# ProProject_Buck-Boost_1_2024-04-12.net
KiCad netlist of a schematic drawn in EasyEDA Pro
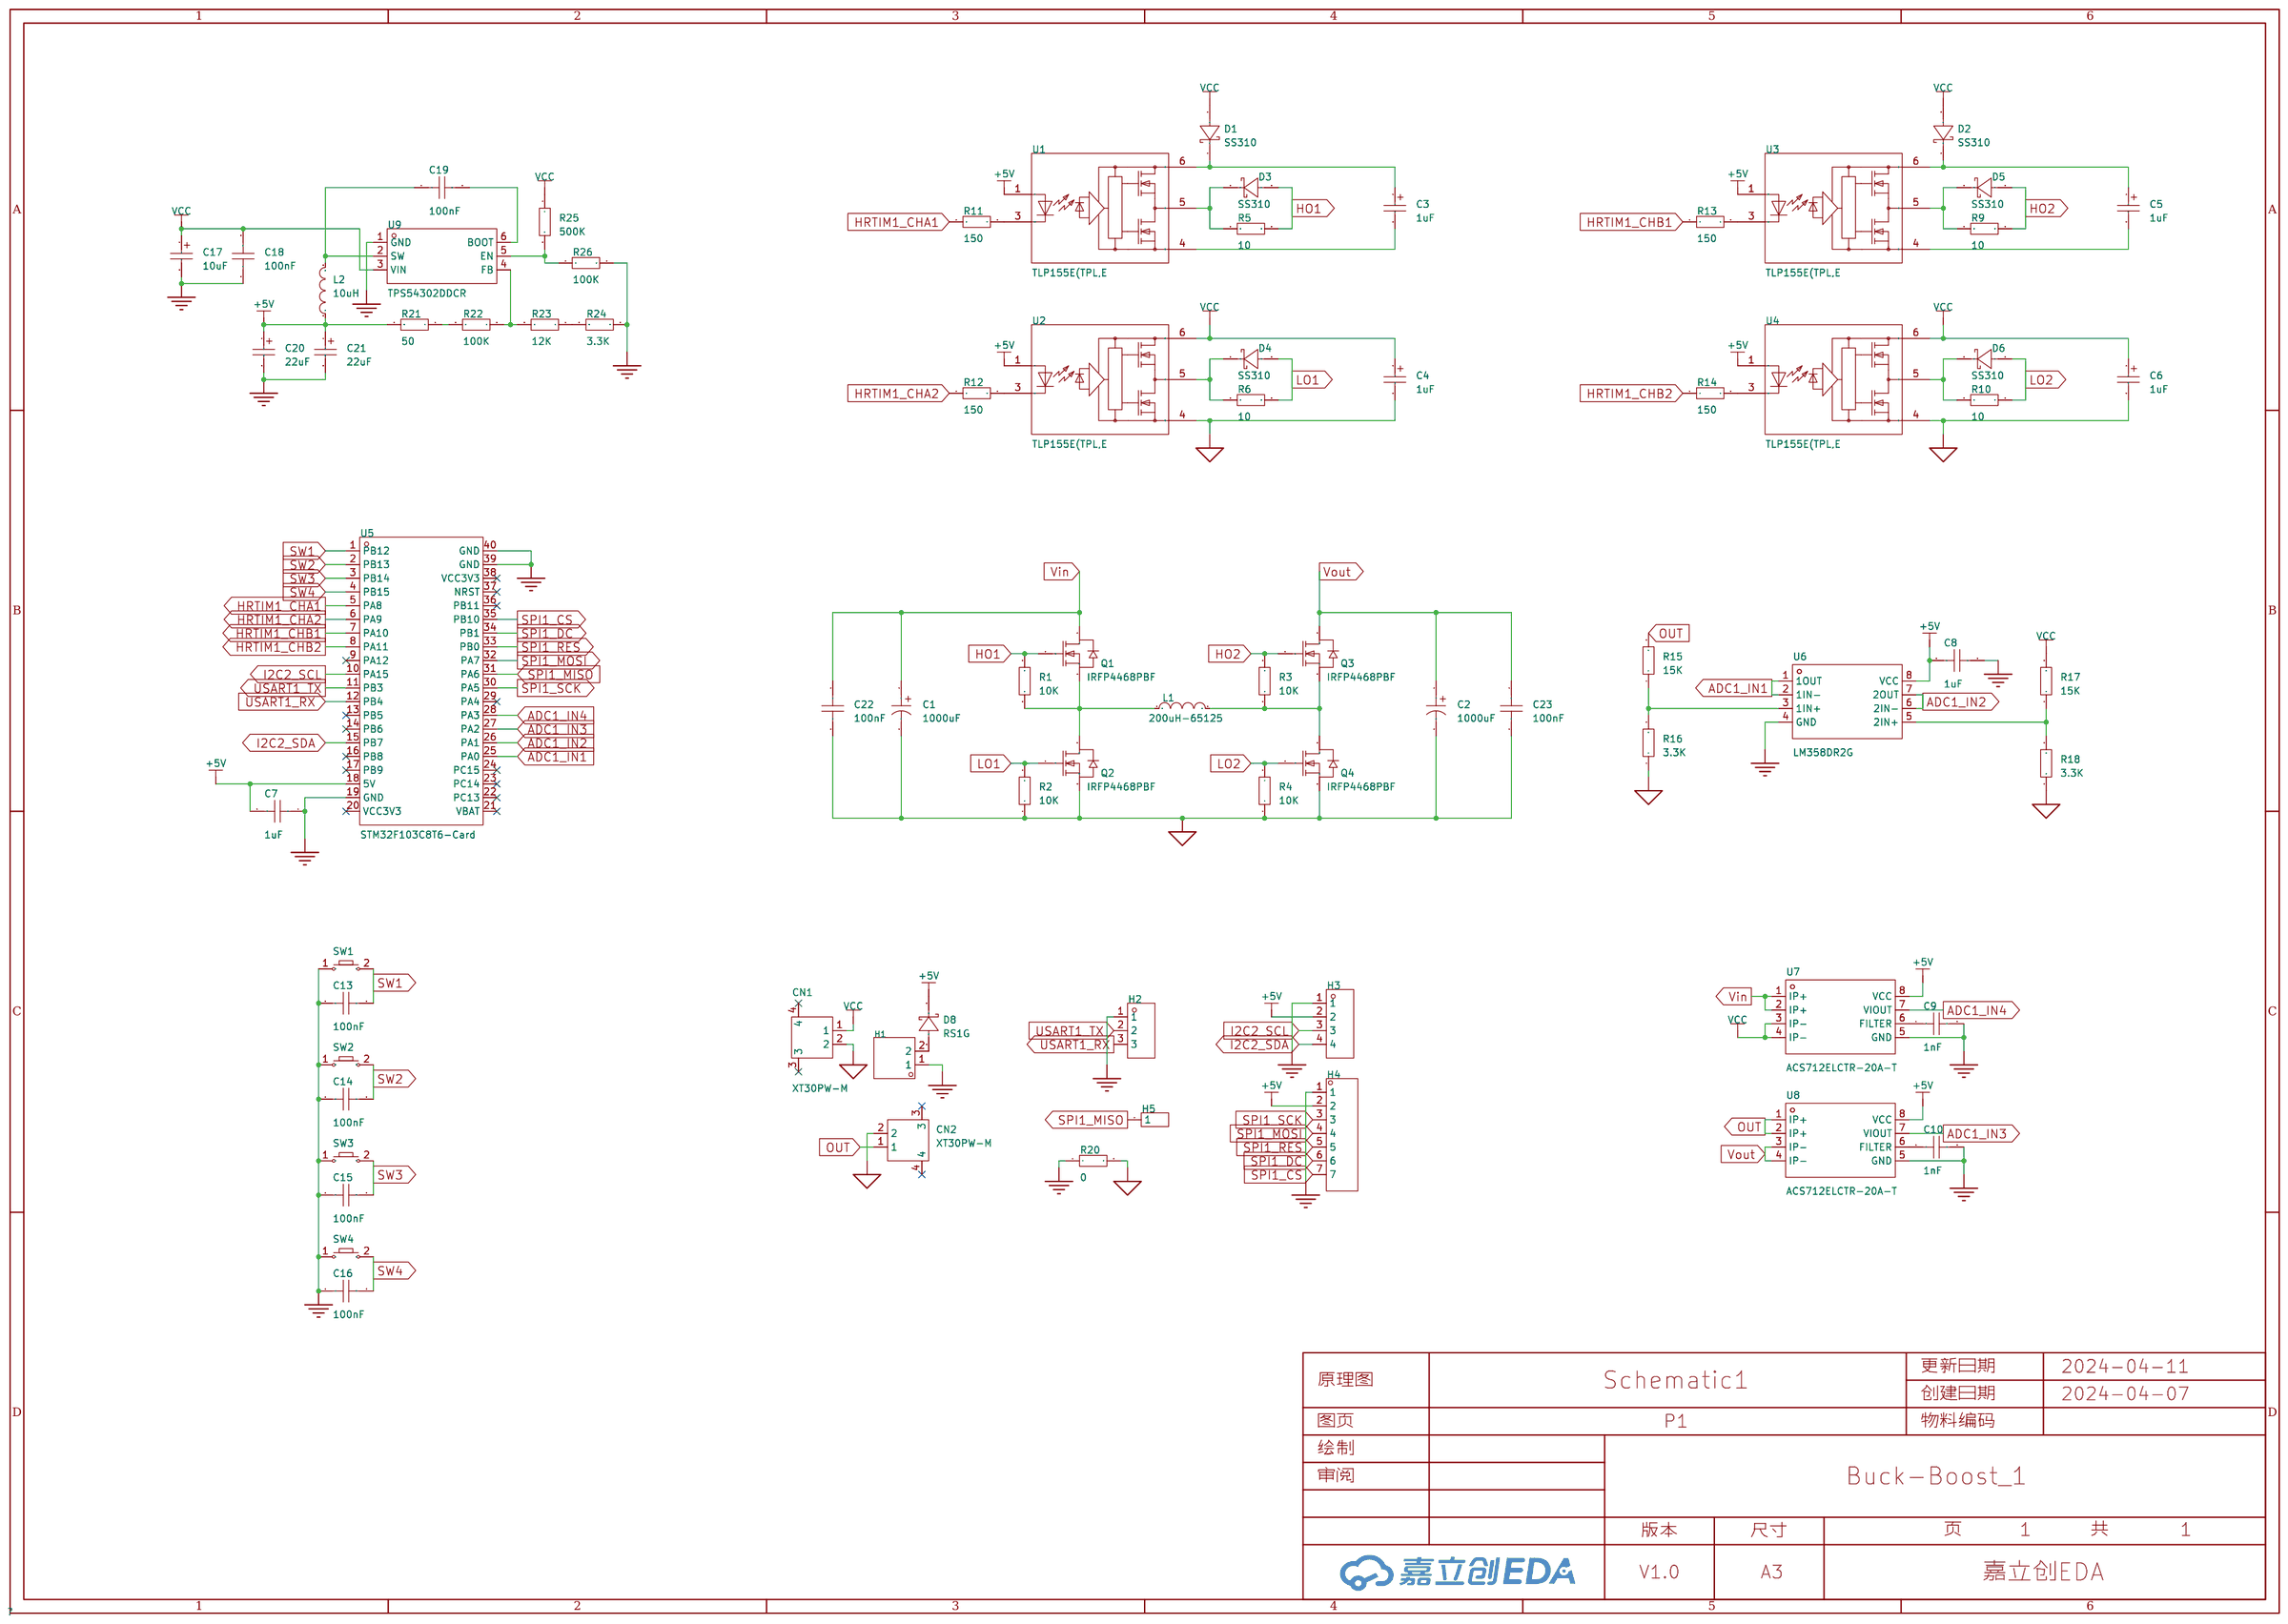
[diagram p0: schematic sheet]

(export (version "E")
  (design (tool "Eeschema 10.0.6"))
  (components
    (comp (ref "C1")
      (value "1000uF")
      (footprint "easyedapro:CAP-TH_BD16.0-P7.50-D1.5-FD")
      (description "容值:470uF;精度:±20%;额定电压:120V;纹波电流:-;等效串联电阻:-;")
      (fields (field (name "Manufacturer Part") "KF102M050I250A") (field (name "Manufacturer") "CapXon(丰宾)"))
      (libsource (lib "easyedapro") (part "ERS2BM471L35OT"))
    )
    (comp (ref "C2")
      (value "1000uF")
      (footprint "easyedapro:CAP-TH_BD16.0-P7.50-D1.5-FD")
      (description "容值:470uF;精度:±20%;额定电压:120V;纹波电流:-;等效串联电阻:-;")
      (fields (field (name "Manufacturer Part") "KF102M050I250A") (field (name "Manufacturer") "CapXon(丰宾)"))
      (libsource (lib "easyedapro") (part "ERS2BM471L35OT"))
    )
    (comp (ref "C3")
      (value "1uF")
      (footprint "easyedapro:CASE-A_3216")
      (description "容值:1uF;精度:±10%;额定电压:35V;等效串联电阻:7.5Ω@100kHz;")
      (fields (field (name "Manufacturer Part") "TAJA105K035RNJ") (field (name "Manufacturer") "Kyocera AVX"))
      (libsource (lib "easyedapro") (part "TAJA105K035RNJ"))
    )
    (comp (ref "C4")
      (value "1uF")
      (footprint "easyedapro:CASE-A_3216")
      (description "容值:1uF;精度:±10%;额定电压:35V;等效串联电阻:7.5Ω@100kHz;")
      (fields (field (name "Manufacturer Part") "TAJA105K035RNJ") (field (name "Manufacturer") "Kyocera AVX"))
      (libsource (lib "easyedapro") (part "TAJA105K035RNJ"))
    )
    (comp (ref "C5")
      (value "1uF")
      (footprint "easyedapro:CASE-A_3216")
      (description "容值:1uF;精度:±10%;额定电压:35V;等效串联电阻:7.5Ω@100kHz;")
      (fields (field (name "Manufacturer Part") "TAJA105K035RNJ") (field (name "Manufacturer") "Kyocera AVX"))
      (libsource (lib "easyedapro") (part "TAJA105K035RNJ"))
    )
    (comp (ref "C6")
      (value "1uF")
      (footprint "easyedapro:CASE-A_3216")
      (description "容值:1uF;精度:±10%;额定电压:35V;等效串联电阻:7.5Ω@100kHz;")
      (fields (field (name "Manufacturer Part") "TAJA105K035RNJ") (field (name "Manufacturer") "Kyocera AVX"))
      (libsource (lib "easyedapro") (part "TAJA105K035RNJ"))
    )
    (comp (ref "C7")
      (value "1uF")
      (footprint "easyedapro:C0805")
      (libsource (lib "easyedapro") (part "CapAcitance"))
    )
    (comp (ref "C8")
      (value "1uF")
      (footprint "easyedapro:C0805")
      (libsource (lib "easyedapro") (part "CapAcitance"))
    )
    (comp (ref "C9")
      (value "1nF")
      (footprint "easyedapro:C0805")
      (libsource (lib "easyedapro") (part "CapAcitance"))
    )
    (comp (ref "C10")
      (value "1nF")
      (footprint "easyedapro:C0805")
      (libsource (lib "easyedapro") (part "CapAcitance"))
    )
    (comp (ref "C13")
      (value "100nF")
      (footprint "easyedapro:C0805")
      (libsource (lib "easyedapro") (part "CapAcitance"))
    )
    (comp (ref "C14")
      (value "100nF")
      (footprint "easyedapro:C0805")
      (libsource (lib "easyedapro") (part "CapAcitance"))
    )
    (comp (ref "C15")
      (value "100nF")
      (footprint "easyedapro:C0805")
      (libsource (lib "easyedapro") (part "CapAcitance"))
    )
    (comp (ref "C16")
      (value "100nF")
      (footprint "easyedapro:C0805")
      (libsource (lib "easyedapro") (part "CapAcitance"))
    )
    (comp (ref "C17")
      (value "10uF")
      (footprint "easyedapro:CAP-SMD_L3.5-W2.8-R-RD")
      (description "容值:10uF;精度:±10%;额定电压:25V;等效串联电阻:2.5Ω@100kHz;")
      (fields (field (name "Manufacturer Part") "TAJB106K025RNJ") (field (name "Manufacturer") "Kyocera AVX"))
      (libsource (lib "easyedapro") (part "TAJB106K025RNJ"))
    )
    (comp (ref "C18")
      (value "100nF")
      (footprint "easyedapro:C0805")
      (libsource (lib "easyedapro") (part "CapAcitance"))
    )
    (comp (ref "C19")
      (value "100nF")
      (footprint "easyedapro:C0805")
      (libsource (lib "easyedapro") (part "CapAcitance"))
    )
    (comp (ref "C20")
      (value "22uF")
      (footprint "easyedapro:CASE-B_3528")
      (description "容值:22uF;精度:±10%;额定电压:16V;等效串联电阻:2.3Ω@100kHz;")
      (fields (field (name "Manufacturer Part") "TAJB226K016RNJ") (field (name "Manufacturer") "Kyocera AVX"))
      (libsource (lib "easyedapro") (part "TAJB226K016RNJ"))
    )
    (comp (ref "C21")
      (value "22uF")
      (footprint "easyedapro:CASE-B_3528")
      (description "容值:22uF;精度:±10%;额定电压:16V;等效串联电阻:2.3Ω@100kHz;")
      (fields (field (name "Manufacturer Part") "TAJB226K016RNJ") (field (name "Manufacturer") "Kyocera AVX"))
      (libsource (lib "easyedapro") (part "TAJB226K016RNJ"))
    )
    (comp (ref "C22")
      (value "100nF")
      (footprint "easyedapro:C0805")
      (libsource (lib "easyedapro") (part "CapAcitance"))
    )
    (comp (ref "C23")
      (value "100nF")
      (footprint "easyedapro:C0805")
      (libsource (lib "easyedapro") (part "CapAcitance"))
    )
    (comp (ref "CN1")
      (value "XT30PW-M")
      (footprint "easyedapro:CONN-TH_XT30PW-M")
      (description "类别:-;类型1:-;")
      (fields (field (name "Manufacturer") "AMASS(艾迈斯)"))
      (libsource (lib "easyedapro") (part "XT30PW-M"))
    )
    (comp (ref "CN2")
      (value "XT30PW-M")
      (footprint "easyedapro:CONN-TH_XT30PW-M")
      (description "类别:-;类型1:-;")
      (fields (field (name "Manufacturer") "AMASS(艾迈斯)"))
      (libsource (lib "easyedapro") (part "XT30PW-M"))
    )
    (comp (ref "D1")
      (value "SS310")
      (footprint "easyedapro:SMC_L6.9-W5.9-LS7.9-RD")
      (fields (field (name "Manufacturer") "MDD"))
      (libsource (lib "easyedapro") (part "SS56_C5161914"))
    )
    (comp (ref "D2")
      (value "SS310")
      (footprint "easyedapro:SMC_L6.9-W5.9-LS7.9-RD")
      (fields (field (name "Manufacturer") "MDD"))
      (libsource (lib "easyedapro") (part "SS56_C5161914"))
    )
    (comp (ref "D3")
      (value "SS310")
      (footprint "easyedapro:SMC_L6.9-W5.9-LS7.9-RD")
      (fields (field (name "Manufacturer") "MDD"))
      (libsource (lib "easyedapro") (part "SS56_C5161914"))
    )
    (comp (ref "D4")
      (value "SS310")
      (footprint "easyedapro:SMC_L6.9-W5.9-LS7.9-RD")
      (fields (field (name "Manufacturer") "MDD"))
      (libsource (lib "easyedapro") (part "SS56_C5161914"))
    )
    (comp (ref "D5")
      (value "SS310")
      (footprint "easyedapro:SMC_L6.9-W5.9-LS7.9-RD")
      (fields (field (name "Manufacturer") "MDD"))
      (libsource (lib "easyedapro") (part "SS56_C5161914"))
    )
    (comp (ref "D6")
      (value "SS310")
      (footprint "easyedapro:SMC_L6.9-W5.9-LS7.9-RD")
      (fields (field (name "Manufacturer") "MDD"))
      (libsource (lib "easyedapro") (part "SS56_C5161914"))
    )
    (comp (ref "D8")
      (value "RS1G")
      (footprint "easyedapro:SMC_L6.9-W5.9-LS7.9-RD")
      (fields (field (name "Manufacturer") "宏迦橙"))
      (libsource (lib "easyedapro") (part "SS56_C5161914"))
    )
    (comp (ref "H1")
      (value "~")
      (footprint "easyedapro:HDR-TH_2P-P2.54-V-M-1")
      (libsource (lib "easyedapro") (part "210S-1*2P L=11.6MMGold-plated black"))
    )
    (comp (ref "H2")
      (value "~")
      (footprint "easyedapro:HDR-TH_3P-P2.54-V-M")
      (libsource (lib "easyedapro") (part "PZ254V-11-03P_C2937625"))
    )
    (comp (ref "H3")
      (value "~")
      (footprint "easyedapro:HDR-TH_4P-P2.54-V-F")
      (libsource (lib "easyedapro") (part "2.54-1*4P母"))
    )
    (comp (ref "H4")
      (value "~")
      (footprint "easyedapro:HDR-TH_7P-P2.54-V-F")
      (libsource (lib "easyedapro") (part "220S-1*7P H=8.5MM Ytype Gold-plated"))
    )
    (comp (ref "H5")
      (value "~")
      (footprint "easyedapro:HDR-TH_1P-V-M_XKB_X4611WV-01I-C28D40")
      (libsource (lib "easyedapro") (part "HDR_1x1"))
    )
    (comp (ref "L1")
      (value "200uH-65125")
      (footprint "easyedapro:IND-TH_200UH-65125")
      (libsource (lib "easyedapro") (part "200UH-65125"))
    )
    (comp (ref "L2")
      (value "10uH")
      (footprint "easyedapro:IND-SMD_L7.3-W6.8")
      (description "电感值:10uH;精度:±20%;额定电流:4.5A;饱和电流(Isat):5.5A;类型:一体成型电感;")
      (fields (field (name "Manufacturer Part") "FXL0630-100-M") (field (name "Manufacturer") "cjiang(长江微电)"))
      (libsource (lib "easyedapro") (part "FXL0630-100-M"))
    )
    (comp (ref "Q1")
      (value "IRFP4468PBF")
      (footprint "easyedapro:TO-247AC-3_L15.8-W5.0-P5.46-L")
      (fields (field (name "Manufacturer") "Infineon(英飞凌)"))
      (libsource (lib "easyedapro") (part "IRFP4468PBF"))
    )
    (comp (ref "Q2")
      (value "IRFP4468PBF")
      (footprint "easyedapro:TO-247AC-3_L15.8-W5.0-P5.46-L")
      (fields (field (name "Manufacturer") "Infineon(英飞凌)"))
      (libsource (lib "easyedapro") (part "IRFP4468PBF"))
    )
    (comp (ref "Q3")
      (value "IRFP4468PBF")
      (footprint "easyedapro:TO-247AC-3_L15.8-W5.0-P5.46-L")
      (fields (field (name "Manufacturer") "Infineon(英飞凌)"))
      (libsource (lib "easyedapro") (part "IRFP4468PBF"))
    )
    (comp (ref "Q4")
      (value "IRFP4468PBF")
      (footprint "easyedapro:TO-247AC-3_L15.8-W5.0-P5.46-L")
      (fields (field (name "Manufacturer") "Infineon(英飞凌)"))
      (libsource (lib "easyedapro") (part "IRFP4468PBF"))
    )
    (comp (ref "R1") (value "10K") (footprint "easyedapro:R0805") (libsource (lib "easyedapro") (part "电阻")))
    (comp (ref "R2") (value "10K") (footprint "easyedapro:R0805") (libsource (lib "easyedapro") (part "电阻")))
    (comp (ref "R3") (value "10K") (footprint "easyedapro:R0805") (libsource (lib "easyedapro") (part "电阻")))
    (comp (ref "R4") (value "10K") (footprint "easyedapro:R0805") (libsource (lib "easyedapro") (part "电阻")))
    (comp (ref "R5") (value "10") (footprint "easyedapro:R0805") (libsource (lib "easyedapro") (part "电阻")))
    (comp (ref "R6") (value "10") (footprint "easyedapro:R0805") (libsource (lib "easyedapro") (part "电阻")))
    (comp (ref "R9") (value "10") (footprint "easyedapro:R0805") (libsource (lib "easyedapro") (part "电阻")))
    (comp (ref "R10") (value "10") (footprint "easyedapro:R0805") (libsource (lib "easyedapro") (part "电阻")))
    (comp (ref "R11") (value "150") (footprint "easyedapro:R0805") (libsource (lib "easyedapro") (part "电阻")))
    (comp (ref "R12") (value "150") (footprint "easyedapro:R0805") (libsource (lib "easyedapro") (part "电阻")))
    (comp (ref "R13") (value "150") (footprint "easyedapro:R0805") (libsource (lib "easyedapro") (part "电阻")))
    (comp (ref "R14") (value "150") (footprint "easyedapro:R0805") (libsource (lib "easyedapro") (part "电阻")))
    (comp (ref "R15") (value "15K") (footprint "easyedapro:R0805") (libsource (lib "easyedapro") (part "电阻")))
    (comp (ref "R16")
      (value "3.3K")
      (footprint "easyedapro:R0805")
      (libsource (lib "easyedapro") (part "电阻"))
    )
    (comp (ref "R17") (value "15K") (footprint "easyedapro:R0805") (libsource (lib "easyedapro") (part "电阻")))
    (comp (ref "R18")
      (value "3.3K")
      (footprint "easyedapro:R0805")
      (libsource (lib "easyedapro") (part "电阻"))
    )
    (comp (ref "R20") (value "0") (footprint "easyedapro:R0805") (libsource (lib "easyedapro") (part "电阻")))
    (comp (ref "R21") (value "50") (footprint "easyedapro:R0805") (libsource (lib "easyedapro") (part "电阻")))
    (comp (ref "R22")
      (value "100K")
      (footprint "easyedapro:R0805")
      (libsource (lib "easyedapro") (part "电阻"))
    )
    (comp (ref "R23") (value "12K") (footprint "easyedapro:R0805") (libsource (lib "easyedapro") (part "电阻")))
    (comp (ref "R24")
      (value "3.3K")
      (footprint "easyedapro:R0805")
      (libsource (lib "easyedapro") (part "电阻"))
    )
    (comp (ref "R25")
      (value "500K")
      (footprint "easyedapro:R0805")
      (libsource (lib "easyedapro") (part "电阻"))
    )
    (comp (ref "R26")
      (value "100K")
      (footprint "easyedapro:R0805")
      (libsource (lib "easyedapro") (part "电阻"))
    )
    (comp (ref "SW1")
      (value "~")
      (footprint "easyedapro:Key_SMD_3x4x2")
      (libsource (lib "easyedapro") (part "轻触按键x2"))
    )
    (comp (ref "SW2")
      (value "~")
      (footprint "easyedapro:Key_SMD_3x4x2")
      (libsource (lib "easyedapro") (part "轻触按键x2"))
    )
    (comp (ref "SW3")
      (value "~")
      (footprint "easyedapro:Key_SMD_3x4x2")
      (libsource (lib "easyedapro") (part "轻触按键x2"))
    )
    (comp (ref "SW4")
      (value "~")
      (footprint "easyedapro:Key_SMD_3x4x2")
      (libsource (lib "easyedapro") (part "轻触按键x2"))
    )
    (comp (ref "U1")
      (value "TLP155E(TPL,E")
      (footprint "easyedapro:OPTO-SMD-5_L3.7-W4.6-P1.27-LS7.0-BR")
      (description "输入类型:DC;电源电压:10V~30V;共模瞬变抗扰度CMTI:15kV/us;传播延迟tpLH/tpHL:170ns；170ns;")
      (fields (field (name "Manufacturer") "TOSHIBA(东芝)"))
      (libsource (lib "easyedapro") (part "TLP155E(TPL,E"))
    )
    (comp (ref "U2")
      (value "TLP155E(TPL,E")
      (footprint "easyedapro:OPTO-SMD-5_L3.7-W4.6-P1.27-LS7.0-BR")
      (description "输入类型:DC;电源电压:10V~30V;共模瞬变抗扰度CMTI:15kV/us;传播延迟tpLH/tpHL:170ns；170ns;")
      (fields (field (name "Manufacturer") "TOSHIBA(东芝)"))
      (libsource (lib "easyedapro") (part "TLP155E(TPL,E"))
    )
    (comp (ref "U3")
      (value "TLP155E(TPL,E")
      (footprint "easyedapro:OPTO-SMD-5_L3.7-W4.6-P1.27-LS7.0-BR")
      (description "输入类型:DC;电源电压:10V~30V;共模瞬变抗扰度CMTI:15kV/us;传播延迟tpLH/tpHL:170ns；170ns;")
      (fields (field (name "Manufacturer") "TOSHIBA(东芝)"))
      (libsource (lib "easyedapro") (part "TLP155E(TPL,E"))
    )
    (comp (ref "U4")
      (value "TLP155E(TPL,E")
      (footprint "easyedapro:OPTO-SMD-5_L3.7-W4.6-P1.27-LS7.0-BR")
      (description "输入类型:DC;电源电压:10V~30V;共模瞬变抗扰度CMTI:15kV/us;传播延迟tpLH/tpHL:170ns；170ns;")
      (fields (field (name "Manufacturer") "TOSHIBA(东芝)"))
      (libsource (lib "easyedapro") (part "TLP155E(TPL,E"))
    )
    (comp (ref "U5")
      (value "STM32F103C8T6-Card")
      (footprint "easyedapro:CONN-TH_L53.3-W22.9_STM32F103C8T6-CARD")
      (libsource (lib "easyedapro") (part "STM32F103C8T6-CARD"))
    )
    (comp (ref "U6")
      (value "LM358DR2G")
      (footprint "easyedapro:SOIC-8_L5.0-W4.0-P1.27-LS6.0-BL")
      (description "放大器数:双路;增益带宽积(GBP):1MHz;输入偏置电流(Ib):45nA;压摆率(SR):-;带宽(-3db):-;")
      (fields (field (name "Manufacturer") "onsemi(安森美)"))
      (libsource (lib "easyedapro") (part "LM358DR2G"))
    )
    (comp (ref "U7")
      (value "ACS712ELCTR-20A-T")
      (footprint "easyedapro:SOIC-8_L4.9-W3.9-P1.27-LS6.0-BL")
      (description "电流测量范围:20A;灵敏度:100mV/A;")
      (fields (field (name "Manufacturer") "ALLEGRO(美国埃戈罗)"))
      (libsource (lib "easyedapro") (part "ACS712ELCTR-20A-T"))
    )
    (comp (ref "U8")
      (value "ACS712ELCTR-20A-T")
      (footprint "easyedapro:SOIC-8_L4.9-W3.9-P1.27-LS6.0-BL")
      (description "电流测量范围:20A;灵敏度:100mV/A;")
      (fields (field (name "Manufacturer") "ALLEGRO(美国埃戈罗)"))
      (libsource (lib "easyedapro") (part "ACS712ELCTR-20A-T"))
    )
    (comp (ref "U9")
      (value "TPS54302DDCR")
      (footprint "easyedapro:SOT-23-6_L2.9-W1.6-P0.95-LS2.8-BL")
      (description "功能类型:降压型;输出类型:可调;输入电压:4.5V~28V;输出电压:596mV~28V;输出电流(最大值):3A;")
      (fields (field (name "Manufacturer") "TI(德州仪器)"))
      (libsource (lib "easyedapro") (part "TPS54302DDCR_C311983"))
    )
  )
  (nets
    (net (code "1") (name "+5V") (class "Default")
      (node (ref "C20") (pin "1") (pinfunction "1_1") (pintype "input"))
      (node (ref "C21") (pin "1") (pinfunction "1_1") (pintype "input"))
      (node (ref "C7") (pin "2") (pinfunction "2_2") (pintype "input"))
      (node (ref "C8") (pin "1") (pinfunction "1_1") (pintype "input"))
      (node (ref "D8") (pin "1") (pinfunction "K_1") (pintype "unspecified"))
      (node (ref "H3") (pin "2") (pinfunction "2_2") (pintype "unspecified"))
      (node (ref "H4") (pin "2") (pinfunction "2_2") (pintype "unspecified"))
      (node (ref "L2") (pin "1") (pinfunction "1_1") (pintype "unspecified"))
      (node (ref "R21") (pin "2") (pinfunction "2_2") (pintype "input"))
      (node (ref "U1") (pin "1") (pinfunction "AN_1") (pintype "unspecified"))
      (node (ref "U2") (pin "1") (pinfunction "AN_1") (pintype "unspecified"))
      (node (ref "U3") (pin "1") (pinfunction "AN_1") (pintype "unspecified"))
      (node (ref "U4") (pin "1") (pinfunction "AN_1") (pintype "unspecified"))
      (node (ref "U5") (pin "18") (pinfunction "5V_18") (pintype "unspecified"))
      (node (ref "U6") (pin "8") (pinfunction "VCC_8") (pintype "unspecified"))
      (node (ref "U7") (pin "8") (pinfunction "VCC_8") (pintype "unspecified"))
      (node (ref "U8") (pin "8") (pinfunction "VCC_8") (pintype "unspecified"))
    )
    (net (code "2") (name "ADC1_IN1") (class "Default")
      (node (ref "U5") (pin "25") (pinfunction "PA0_25") (pintype "unspecified"))
      (node (ref "U6") (pin "1") (pinfunction "1OUT_1") (pintype "unspecified"))
      (node (ref "U6") (pin "2") (pinfunction "1IN-_2") (pintype "unspecified"))
    )
    (net (code "3") (name "ADC1_IN2") (class "Default")
      (node (ref "U5") (pin "26") (pinfunction "PA1_26") (pintype "unspecified"))
      (node (ref "U6") (pin "6") (pinfunction "2IN-_6") (pintype "unspecified"))
      (node (ref "U6") (pin "7") (pinfunction "2OUT_7") (pintype "unspecified"))
    )
    (net (code "4") (name "ADC1_IN3") (class "Default")
      (node (ref "U5") (pin "27") (pinfunction "PA2_27") (pintype "unspecified"))
      (node (ref "U8") (pin "7") (pinfunction "VIOUT_7") (pintype "unspecified"))
    )
    (net (code "5") (name "ADC1_IN4") (class "Default")
      (node (ref "U5") (pin "28") (pinfunction "PA3_28") (pintype "unspecified"))
      (node (ref "U7") (pin "7") (pinfunction "VIOUT_7") (pintype "unspecified"))
    )
    (net (code "6") (name "AGND") (class "Default")
      (node (ref "C1") (pin "2") (pinfunction "2_2") (pintype "input"))
      (node (ref "C2") (pin "2") (pinfunction "2_2") (pintype "input"))
      (node (ref "C22") (pin "2") (pinfunction "2_2") (pintype "input"))
      (node (ref "C23") (pin "2") (pinfunction "2_2") (pintype "input"))
      (node (ref "C4") (pin "2") (pinfunction "2_2") (pintype "input"))
      (node (ref "C6") (pin "2") (pinfunction "2_2") (pintype "input"))
      (node (ref "CN1") (pin "2") (pinfunction "2_2") (pintype "unspecified"))
      (node (ref "CN2") (pin "2") (pinfunction "2_2") (pintype "unspecified"))
      (node (ref "Q2") (pin "3") (pinfunction "S_3") (pintype "unspecified"))
      (node (ref "Q4") (pin "3") (pinfunction "S_3") (pintype "unspecified"))
      (node (ref "R16") (pin "1") (pinfunction "1_1") (pintype "input"))
      (node (ref "R18") (pin "1") (pinfunction "1_1") (pintype "input"))
      (node (ref "R2") (pin "1") (pinfunction "1_1") (pintype "input"))
      (node (ref "R20") (pin "2") (pinfunction "2_2") (pintype "input"))
      (node (ref "R4") (pin "1") (pinfunction "1_1") (pintype "input"))
      (node (ref "U2") (pin "4") (pinfunction "GND_4") (pintype "unspecified"))
      (node (ref "U4") (pin "4") (pinfunction "GND_4") (pintype "unspecified"))
    )
    (net (code "7") (name "GND") (class "Default")
      (node (ref "C10") (pin "2") (pinfunction "2_2") (pintype "input"))
      (node (ref "C13") (pin "1") (pinfunction "1_1") (pintype "input"))
      (node (ref "C14") (pin "1") (pinfunction "1_1") (pintype "input"))
      (node (ref "C15") (pin "1") (pinfunction "1_1") (pintype "input"))
      (node (ref "C16") (pin "1") (pinfunction "1_1") (pintype "input"))
      (node (ref "C17") (pin "2") (pinfunction "2_2") (pintype "input"))
      (node (ref "C18") (pin "1") (pinfunction "1_1") (pintype "input"))
      (node (ref "C20") (pin "2") (pinfunction "2_2") (pintype "input"))
      (node (ref "C21") (pin "2") (pinfunction "2_2") (pintype "input"))
      (node (ref "C7") (pin "1") (pinfunction "1_1") (pintype "input"))
      (node (ref "C8") (pin "2") (pinfunction "2_2") (pintype "input"))
      (node (ref "C9") (pin "2") (pinfunction "2_2") (pintype "input"))
      (node (ref "H1") (pin "1") (pinfunction "1_1") (pintype "input"))
      (node (ref "H2") (pin "1") (pinfunction "1_1") (pintype "input"))
      (node (ref "H3") (pin "1") (pinfunction "1_1") (pintype "unspecified"))
      (node (ref "H4") (pin "1") (pinfunction "1_1") (pintype "unspecified"))
      (node (ref "R20") (pin "1") (pinfunction "1_1") (pintype "input"))
      (node (ref "R24") (pin "2") (pinfunction "2_2") (pintype "input"))
      (node (ref "R26") (pin "2") (pinfunction "2_2") (pintype "input"))
      (node (ref "SW1") (pin "1") (pinfunction "1_1") (pintype "input"))
      (node (ref "SW2") (pin "1") (pinfunction "1_1") (pintype "input"))
      (node (ref "SW3") (pin "1") (pinfunction "1_1") (pintype "input"))
      (node (ref "SW4") (pin "1") (pinfunction "1_1") (pintype "input"))
      (node (ref "U5") (pin "19") (pinfunction "GND_19") (pintype "unspecified"))
      (node (ref "U5") (pin "39") (pinfunction "GND_39") (pintype "unspecified"))
      (node (ref "U5") (pin "40") (pinfunction "GND_40") (pintype "unspecified"))
      (node (ref "U6") (pin "4") (pinfunction "GND_4") (pintype "unspecified"))
      (node (ref "U7") (pin "5") (pinfunction "GND_5") (pintype "unspecified"))
      (node (ref "U8") (pin "5") (pinfunction "GND_5") (pintype "unspecified"))
      (node (ref "U9") (pin "1") (pinfunction "GND_1") (pintype "unspecified"))
    )
    (net (code "8") (name "HO1") (class "Default")
      (node (ref "D3") (pin "2") (pinfunction "A_2") (pintype "unspecified"))
      (node (ref "Q1") (pin "1") (pinfunction "G_1") (pintype "unspecified"))
      (node (ref "R1") (pin "2") (pinfunction "2_2") (pintype "input"))
      (node (ref "R5") (pin "2") (pinfunction "2_2") (pintype "input"))
    )
    (net (code "9") (name "HO2") (class "Default")
      (node (ref "D5") (pin "2") (pinfunction "A_2") (pintype "unspecified"))
      (node (ref "Q3") (pin "1") (pinfunction "G_1") (pintype "unspecified"))
      (node (ref "R3") (pin "2") (pinfunction "2_2") (pintype "input"))
      (node (ref "R9") (pin "2") (pinfunction "2_2") (pintype "input"))
    )
    (net (code "10") (name "HRTIM1_CHA1") (class "Default")
      (node (ref "R11") (pin "1") (pinfunction "1_1") (pintype "input"))
      (node (ref "U5") (pin "5") (pinfunction "PA8_5") (pintype "unspecified"))
    )
    (net (code "11") (name "HRTIM1_CHA2") (class "Default")
      (node (ref "R12") (pin "1") (pinfunction "1_1") (pintype "input"))
      (node (ref "U5") (pin "6") (pinfunction "PA9_6") (pintype "unspecified"))
    )
    (net (code "12") (name "HRTIM1_CHB1") (class "Default")
      (node (ref "R13") (pin "1") (pinfunction "1_1") (pintype "input"))
      (node (ref "U5") (pin "7") (pinfunction "PA10_7") (pintype "unspecified"))
    )
    (net (code "13") (name "HRTIM1_CHB2") (class "Default")
      (node (ref "R14") (pin "1") (pinfunction "1_1") (pintype "input"))
      (node (ref "U5") (pin "8") (pinfunction "PA11_8") (pintype "unspecified"))
    )
    (net (code "14") (name "I2C2_SCL") (class "Default")
      (node (ref "H3") (pin "3") (pinfunction "3_3") (pintype "unspecified"))
      (node (ref "U5") (pin "10") (pinfunction "PA15_10") (pintype "unspecified"))
    )
    (net (code "15") (name "I2C2_SDA") (class "Default")
      (node (ref "H3") (pin "4") (pinfunction "4_4") (pintype "unspecified"))
      (node (ref "U5") (pin "15") (pinfunction "PB7_15") (pintype "unspecified"))
    )
    (net (code "16") (name "LO1") (class "Default")
      (node (ref "D4") (pin "2") (pinfunction "A_2") (pintype "unspecified"))
      (node (ref "Q2") (pin "1") (pinfunction "G_1") (pintype "unspecified"))
      (node (ref "R2") (pin "2") (pinfunction "2_2") (pintype "input"))
      (node (ref "R6") (pin "2") (pinfunction "2_2") (pintype "input"))
    )
    (net (code "17") (name "LO2") (class "Default")
      (node (ref "D6") (pin "2") (pinfunction "A_2") (pintype "unspecified"))
      (node (ref "Q4") (pin "1") (pinfunction "G_1") (pintype "unspecified"))
      (node (ref "R10") (pin "2") (pinfunction "2_2") (pintype "input"))
      (node (ref "R4") (pin "2") (pinfunction "2_2") (pintype "input"))
    )
    (net (code "18") (name "Net-(D1-K)") (class "Default")
      (node (ref "C3") (pin "1") (pinfunction "1_1") (pintype "input"))
      (node (ref "D1") (pin "1") (pinfunction "K_1") (pintype "unspecified"))
      (node (ref "U1") (pin "6") (pinfunction "VCC_6") (pintype "unspecified"))
    )
    (net (code "19") (name "Net-(D2-K)") (class "Default")
      (node (ref "C5") (pin "1") (pinfunction "1_1") (pintype "input"))
      (node (ref "D2") (pin "1") (pinfunction "K_1") (pintype "unspecified"))
      (node (ref "U3") (pin "6") (pinfunction "VCC_6") (pintype "unspecified"))
    )
    (net (code "20") (name "Net-(D3-K)") (class "Default")
      (node (ref "D3") (pin "1") (pinfunction "K_1") (pintype "unspecified"))
      (node (ref "R5") (pin "1") (pinfunction "1_1") (pintype "input"))
      (node (ref "U1") (pin "5") (pinfunction "VO_5") (pintype "unspecified"))
    )
    (net (code "21") (name "Net-(D4-K)") (class "Default")
      (node (ref "D4") (pin "1") (pinfunction "K_1") (pintype "unspecified"))
      (node (ref "R6") (pin "1") (pinfunction "1_1") (pintype "input"))
      (node (ref "U2") (pin "5") (pinfunction "VO_5") (pintype "unspecified"))
    )
    (net (code "22") (name "Net-(D5-K)") (class "Default")
      (node (ref "D5") (pin "1") (pinfunction "K_1") (pintype "unspecified"))
      (node (ref "R9") (pin "1") (pinfunction "1_1") (pintype "input"))
      (node (ref "U3") (pin "5") (pinfunction "VO_5") (pintype "unspecified"))
    )
    (net (code "23") (name "Net-(D6-K)") (class "Default")
      (node (ref "D6") (pin "1") (pinfunction "K_1") (pintype "unspecified"))
      (node (ref "R10") (pin "1") (pinfunction "1_1") (pintype "input"))
      (node (ref "U4") (pin "5") (pinfunction "VO_5") (pintype "unspecified"))
    )
    (net (code "24") (name "Net-(D8-A)") (class "Default")
      (node (ref "D8") (pin "2") (pinfunction "A_2") (pintype "unspecified"))
      (node (ref "H1") (pin "2") (pinfunction "2_2") (pintype "input"))
    )
    (net (code "25") (name "Net-(Q1-S)") (class "Default")
      (node (ref "L1") (pin "1") (pinfunction "1_1") (pintype "input"))
      (node (ref "Q1") (pin "3") (pinfunction "S_3") (pintype "unspecified"))
      (node (ref "Q2") (pin "2") (pinfunction "D_2") (pintype "unspecified"))
      (node (ref "R1") (pin "1") (pinfunction "1_1") (pintype "input"))
    )
    (net (code "26") (name "Net-(Q3-S)") (class "Default")
      (node (ref "L1") (pin "2") (pinfunction "2_2") (pintype "input"))
      (node (ref "Q3") (pin "3") (pinfunction "S_3") (pintype "unspecified"))
      (node (ref "Q4") (pin "2") (pinfunction "D_2") (pintype "unspecified"))
      (node (ref "R3") (pin "1") (pinfunction "1_1") (pintype "input"))
    )
    (net (code "27") (name "Net-(R21-Pad1)") (class "Default")
      (node (ref "R21") (pin "1") (pinfunction "1_1") (pintype "input"))
      (node (ref "R22") (pin "2") (pinfunction "2_2") (pintype "input"))
    )
    (net (code "28") (name "Net-(R23-Pad1)") (class "Default")
      (node (ref "R23") (pin "1") (pinfunction "1_1") (pintype "input"))
      (node (ref "R24") (pin "1") (pinfunction "1_1") (pintype "input"))
    )
    (net (code "29") (name "Net-(U1-CAT)") (class "Default")
      (node (ref "R11") (pin "2") (pinfunction "2_2") (pintype "input"))
      (node (ref "U1") (pin "3") (pinfunction "CAT_3") (pintype "unspecified"))
    )
    (net (code "30") (name "Net-(U1-GND)") (class "Default")
      (node (ref "C3") (pin "2") (pinfunction "2_2") (pintype "input"))
      (node (ref "U1") (pin "4") (pinfunction "GND_4") (pintype "unspecified"))
    )
    (net (code "31") (name "Net-(U2-CAT)") (class "Default")
      (node (ref "R12") (pin "2") (pinfunction "2_2") (pintype "input"))
      (node (ref "U2") (pin "3") (pinfunction "CAT_3") (pintype "unspecified"))
    )
    (net (code "32") (name "Net-(U3-CAT)") (class "Default")
      (node (ref "R13") (pin "2") (pinfunction "2_2") (pintype "input"))
      (node (ref "U3") (pin "3") (pinfunction "CAT_3") (pintype "unspecified"))
    )
    (net (code "33") (name "Net-(U3-GND)") (class "Default")
      (node (ref "C5") (pin "2") (pinfunction "2_2") (pintype "input"))
      (node (ref "U3") (pin "4") (pinfunction "GND_4") (pintype "unspecified"))
    )
    (net (code "34") (name "Net-(U4-CAT)") (class "Default")
      (node (ref "R14") (pin "2") (pinfunction "2_2") (pintype "input"))
      (node (ref "U4") (pin "3") (pinfunction "CAT_3") (pintype "unspecified"))
    )
    (net (code "35") (name "Net-(U6-1IN+)") (class "Default")
      (node (ref "R15") (pin "1") (pinfunction "1_1") (pintype "input"))
      (node (ref "R16") (pin "2") (pinfunction "2_2") (pintype "input"))
      (node (ref "U6") (pin "3") (pinfunction "1IN+_3") (pintype "unspecified"))
    )
    (net (code "36") (name "Net-(U6-2IN+)") (class "Default")
      (node (ref "R17") (pin "1") (pinfunction "1_1") (pintype "input"))
      (node (ref "R18") (pin "2") (pinfunction "2_2") (pintype "input"))
      (node (ref "U6") (pin "5") (pinfunction "2IN+_5") (pintype "unspecified"))
    )
    (net (code "37") (name "Net-(U7-FILTER)") (class "Default")
      (node (ref "C9") (pin "1") (pinfunction "1_1") (pintype "input"))
      (node (ref "U7") (pin "6") (pinfunction "FILTER_6") (pintype "unspecified"))
    )
    (net (code "38") (name "Net-(U8-FILTER)") (class "Default")
      (node (ref "C10") (pin "1") (pinfunction "1_1") (pintype "input"))
      (node (ref "U8") (pin "6") (pinfunction "FILTER_6") (pintype "unspecified"))
    )
    (net (code "39") (name "Net-(U9-BOOT)") (class "Default")
      (node (ref "C19") (pin "2") (pinfunction "2_2") (pintype "input"))
      (node (ref "U9") (pin "6") (pinfunction "BOOT_6") (pintype "unspecified"))
    )
    (net (code "40") (name "Net-(U9-EN)") (class "Default")
      (node (ref "R25") (pin "2") (pinfunction "2_2") (pintype "input"))
      (node (ref "R26") (pin "1") (pinfunction "1_1") (pintype "input"))
      (node (ref "U9") (pin "5") (pinfunction "EN_5") (pintype "unspecified"))
    )
    (net (code "41") (name "Net-(U9-FB)") (class "Default")
      (node (ref "R22") (pin "1") (pinfunction "1_1") (pintype "input"))
      (node (ref "R23") (pin "2") (pinfunction "2_2") (pintype "input"))
      (node (ref "U9") (pin "4") (pinfunction "FB_4") (pintype "unspecified"))
    )
    (net (code "42") (name "Net-(U9-SW)") (class "Default")
      (node (ref "C19") (pin "1") (pinfunction "1_1") (pintype "input"))
      (node (ref "L2") (pin "2") (pinfunction "2_2") (pintype "unspecified"))
      (node (ref "U9") (pin "2") (pinfunction "SW_2") (pintype "unspecified"))
    )
    (net (code "43") (name "OUT") (class "Default")
      (node (ref "CN2") (pin "1") (pinfunction "1_1") (pintype "unspecified"))
      (node (ref "R15") (pin "2") (pinfunction "2_2") (pintype "input"))
      (node (ref "U8") (pin "1") (pinfunction "IP+_1") (pintype "unspecified"))
      (node (ref "U8") (pin "2") (pinfunction "IP+_2") (pintype "unspecified"))
    )
    (net (code "44") (name "SPI1_CS") (class "Default")
      (node (ref "H4") (pin "7") (pinfunction "7_7") (pintype "unspecified"))
      (node (ref "U5") (pin "35") (pinfunction "PB10_35") (pintype "unspecified"))
    )
    (net (code "45") (name "SPI1_DC") (class "Default")
      (node (ref "H4") (pin "6") (pinfunction "6_6") (pintype "unspecified"))
      (node (ref "U5") (pin "34") (pinfunction "PB1_34") (pintype "unspecified"))
    )
    (net (code "46") (name "SPI1_MISO") (class "Default")
      (node (ref "H5") (pin "1") (pinfunction "1_1") (pintype "unspecified"))
      (node (ref "U5") (pin "31") (pinfunction "PA6_31") (pintype "unspecified"))
    )
    (net (code "47") (name "SPI1_MOSI") (class "Default")
      (node (ref "H4") (pin "4") (pinfunction "4_4") (pintype "unspecified"))
      (node (ref "U5") (pin "32") (pinfunction "PA7_32") (pintype "unspecified"))
    )
    (net (code "48") (name "SPI1_RES") (class "Default")
      (node (ref "H4") (pin "5") (pinfunction "5_5") (pintype "unspecified"))
      (node (ref "U5") (pin "33") (pinfunction "PB0_33") (pintype "unspecified"))
    )
    (net (code "49") (name "SPI1_SCK") (class "Default")
      (node (ref "H4") (pin "3") (pinfunction "3_3") (pintype "unspecified"))
      (node (ref "U5") (pin "30") (pinfunction "PA5_30") (pintype "unspecified"))
    )
    (net (code "50") (name "SW1") (class "Default")
      (node (ref "C13") (pin "2") (pinfunction "2_2") (pintype "input"))
      (node (ref "SW1") (pin "2") (pinfunction "2_2") (pintype "input"))
      (node (ref "U5") (pin "1") (pinfunction "PB12_1") (pintype "unspecified"))
    )
    (net (code "51") (name "SW2") (class "Default")
      (node (ref "C14") (pin "2") (pinfunction "2_2") (pintype "input"))
      (node (ref "SW2") (pin "2") (pinfunction "2_2") (pintype "input"))
      (node (ref "U5") (pin "2") (pinfunction "PB13_2") (pintype "unspecified"))
    )
    (net (code "52") (name "SW3") (class "Default")
      (node (ref "C15") (pin "2") (pinfunction "2_2") (pintype "input"))
      (node (ref "SW3") (pin "2") (pinfunction "2_2") (pintype "input"))
      (node (ref "U5") (pin "3") (pinfunction "PB14_3") (pintype "unspecified"))
    )
    (net (code "53") (name "SW4") (class "Default")
      (node (ref "C16") (pin "2") (pinfunction "2_2") (pintype "input"))
      (node (ref "SW4") (pin "2") (pinfunction "2_2") (pintype "input"))
      (node (ref "U5") (pin "4") (pinfunction "PB15_4") (pintype "unspecified"))
    )
    (net (code "54") (name "USART1_RX") (class "Default")
      (node (ref "H2") (pin "3") (pinfunction "3_3") (pintype "input"))
      (node (ref "U5") (pin "12") (pinfunction "PB4_12") (pintype "unspecified"))
    )
    (net (code "55") (name "USART1_TX") (class "Default")
      (node (ref "H2") (pin "2") (pinfunction "2_2") (pintype "input"))
      (node (ref "U5") (pin "11") (pinfunction "PB3_11") (pintype "unspecified"))
    )
    (net (code "56") (name "VCC") (class "Default")
      (node (ref "C17") (pin "1") (pinfunction "1_1") (pintype "input"))
      (node (ref "C18") (pin "2") (pinfunction "2_2") (pintype "input"))
      (node (ref "C4") (pin "1") (pinfunction "1_1") (pintype "input"))
      (node (ref "C6") (pin "1") (pinfunction "1_1") (pintype "input"))
      (node (ref "CN1") (pin "1") (pinfunction "1_1") (pintype "unspecified"))
      (node (ref "D1") (pin "2") (pinfunction "A_2") (pintype "unspecified"))
      (node (ref "D2") (pin "2") (pinfunction "A_2") (pintype "unspecified"))
      (node (ref "R17") (pin "2") (pinfunction "2_2") (pintype "input"))
      (node (ref "R25") (pin "1") (pinfunction "1_1") (pintype "input"))
      (node (ref "U2") (pin "6") (pinfunction "VCC_6") (pintype "unspecified"))
      (node (ref "U4") (pin "6") (pinfunction "VCC_6") (pintype "unspecified"))
      (node (ref "U7") (pin "3") (pinfunction "IP-_3") (pintype "unspecified"))
      (node (ref "U7") (pin "4") (pinfunction "IP-_4") (pintype "unspecified"))
      (node (ref "U9") (pin "3") (pinfunction "VIN_3") (pintype "unspecified"))
    )
    (net (code "57") (name "Vin") (class "Default")
      (node (ref "C1") (pin "1") (pinfunction "1_1") (pintype "input"))
      (node (ref "C22") (pin "1") (pinfunction "1_1") (pintype "input"))
      (node (ref "Q1") (pin "2") (pinfunction "D_2") (pintype "unspecified"))
      (node (ref "U7") (pin "1") (pinfunction "IP+_1") (pintype "unspecified"))
      (node (ref "U7") (pin "2") (pinfunction "IP+_2") (pintype "unspecified"))
    )
    (net (code "58") (name "Vout") (class "Default")
      (node (ref "C2") (pin "1") (pinfunction "1_1") (pintype "input"))
      (node (ref "C23") (pin "1") (pinfunction "1_1") (pintype "input"))
      (node (ref "Q3") (pin "2") (pinfunction "D_2") (pintype "unspecified"))
      (node (ref "U8") (pin "3") (pinfunction "IP-_3") (pintype "unspecified"))
      (node (ref "U8") (pin "4") (pinfunction "IP-_4") (pintype "unspecified"))
    )
    (net (code "59") (name "unconnected-(CN1-Pad3)") (class "Default")
      (node (ref "CN1") (pin "3") (pinfunction "3_3") (pintype "unspecified+no_connect"))
    )
    (net (code "60") (name "unconnected-(CN1-Pad4)") (class "Default")
      (node (ref "CN1") (pin "4") (pinfunction "4_4") (pintype "unspecified+no_connect"))
    )
    (net (code "61") (name "unconnected-(CN2-Pad3)") (class "Default")
      (node (ref "CN2") (pin "3") (pinfunction "3_3") (pintype "unspecified+no_connect"))
    )
    (net (code "62") (name "unconnected-(CN2-Pad4)") (class "Default")
      (node (ref "CN2") (pin "4") (pinfunction "4_4") (pintype "unspecified+no_connect"))
    )
    (net (code "63") (name "unconnected-(U5-NRST-Pad37)") (class "Default")
      (node (ref "U5") (pin "37") (pinfunction "NRST_37") (pintype "unspecified+no_connect"))
    )
    (net (code "64") (name "unconnected-(U5-PA4-Pad29)") (class "Default")
      (node (ref "U5") (pin "29") (pinfunction "PA4_29") (pintype "unspecified+no_connect"))
    )
    (net (code "65") (name "unconnected-(U5-PA12-Pad9)") (class "Default")
      (node (ref "U5") (pin "9") (pinfunction "PA12_9") (pintype "unspecified+no_connect"))
    )
    (net (code "66") (name "unconnected-(U5-PB5-Pad13)") (class "Default")
      (node (ref "U5") (pin "13") (pinfunction "PB5_13") (pintype "unspecified+no_connect"))
    )
    (net (code "67") (name "unconnected-(U5-PB6-Pad14)") (class "Default")
      (node (ref "U5") (pin "14") (pinfunction "PB6_14") (pintype "unspecified+no_connect"))
    )
    (net (code "68") (name "unconnected-(U5-PB8-Pad16)") (class "Default")
      (node (ref "U5") (pin "16") (pinfunction "PB8_16") (pintype "unspecified+no_connect"))
    )
    (net (code "69") (name "unconnected-(U5-PB9-Pad17)") (class "Default")
      (node (ref "U5") (pin "17") (pinfunction "PB9_17") (pintype "unspecified+no_connect"))
    )
    (net (code "70") (name "unconnected-(U5-PB11-Pad36)") (class "Default")
      (node (ref "U5") (pin "36") (pinfunction "PB11_36") (pintype "unspecified+no_connect"))
    )
    (net (code "71") (name "unconnected-(U5-PC13-Pad22)") (class "Default")
      (node (ref "U5") (pin "22") (pinfunction "PC13_22") (pintype "unspecified+no_connect"))
    )
    (net (code "72") (name "unconnected-(U5-PC14-Pad23)") (class "Default")
      (node (ref "U5") (pin "23") (pinfunction "PC14_23") (pintype "unspecified+no_connect"))
    )
    (net (code "73") (name "unconnected-(U5-PC15-Pad24)") (class "Default")
      (node (ref "U5") (pin "24") (pinfunction "PC15_24") (pintype "unspecified+no_connect"))
    )
    (net (code "74") (name "unconnected-(U5-VBAT-Pad21)") (class "Default")
      (node (ref "U5") (pin "21") (pinfunction "VBAT_21") (pintype "unspecified+no_connect"))
    )
    (net (code "75") (name "unconnected-(U5-VCC3V3-Pad20)") (class "Default")
      (node (ref "U5") (pin "20") (pinfunction "VCC3V3_20") (pintype "unspecified+no_connect"))
    )
    (net (code "76") (name "unconnected-(U5-VCC3V3-Pad38)") (class "Default")
      (node (ref "U5") (pin "38") (pinfunction "VCC3V3_38") (pintype "unspecified+no_connect"))
    )
  )
)
